# detector_de_IMPACTO.net
KiCad netlist of a schematic drawn in EAGLE
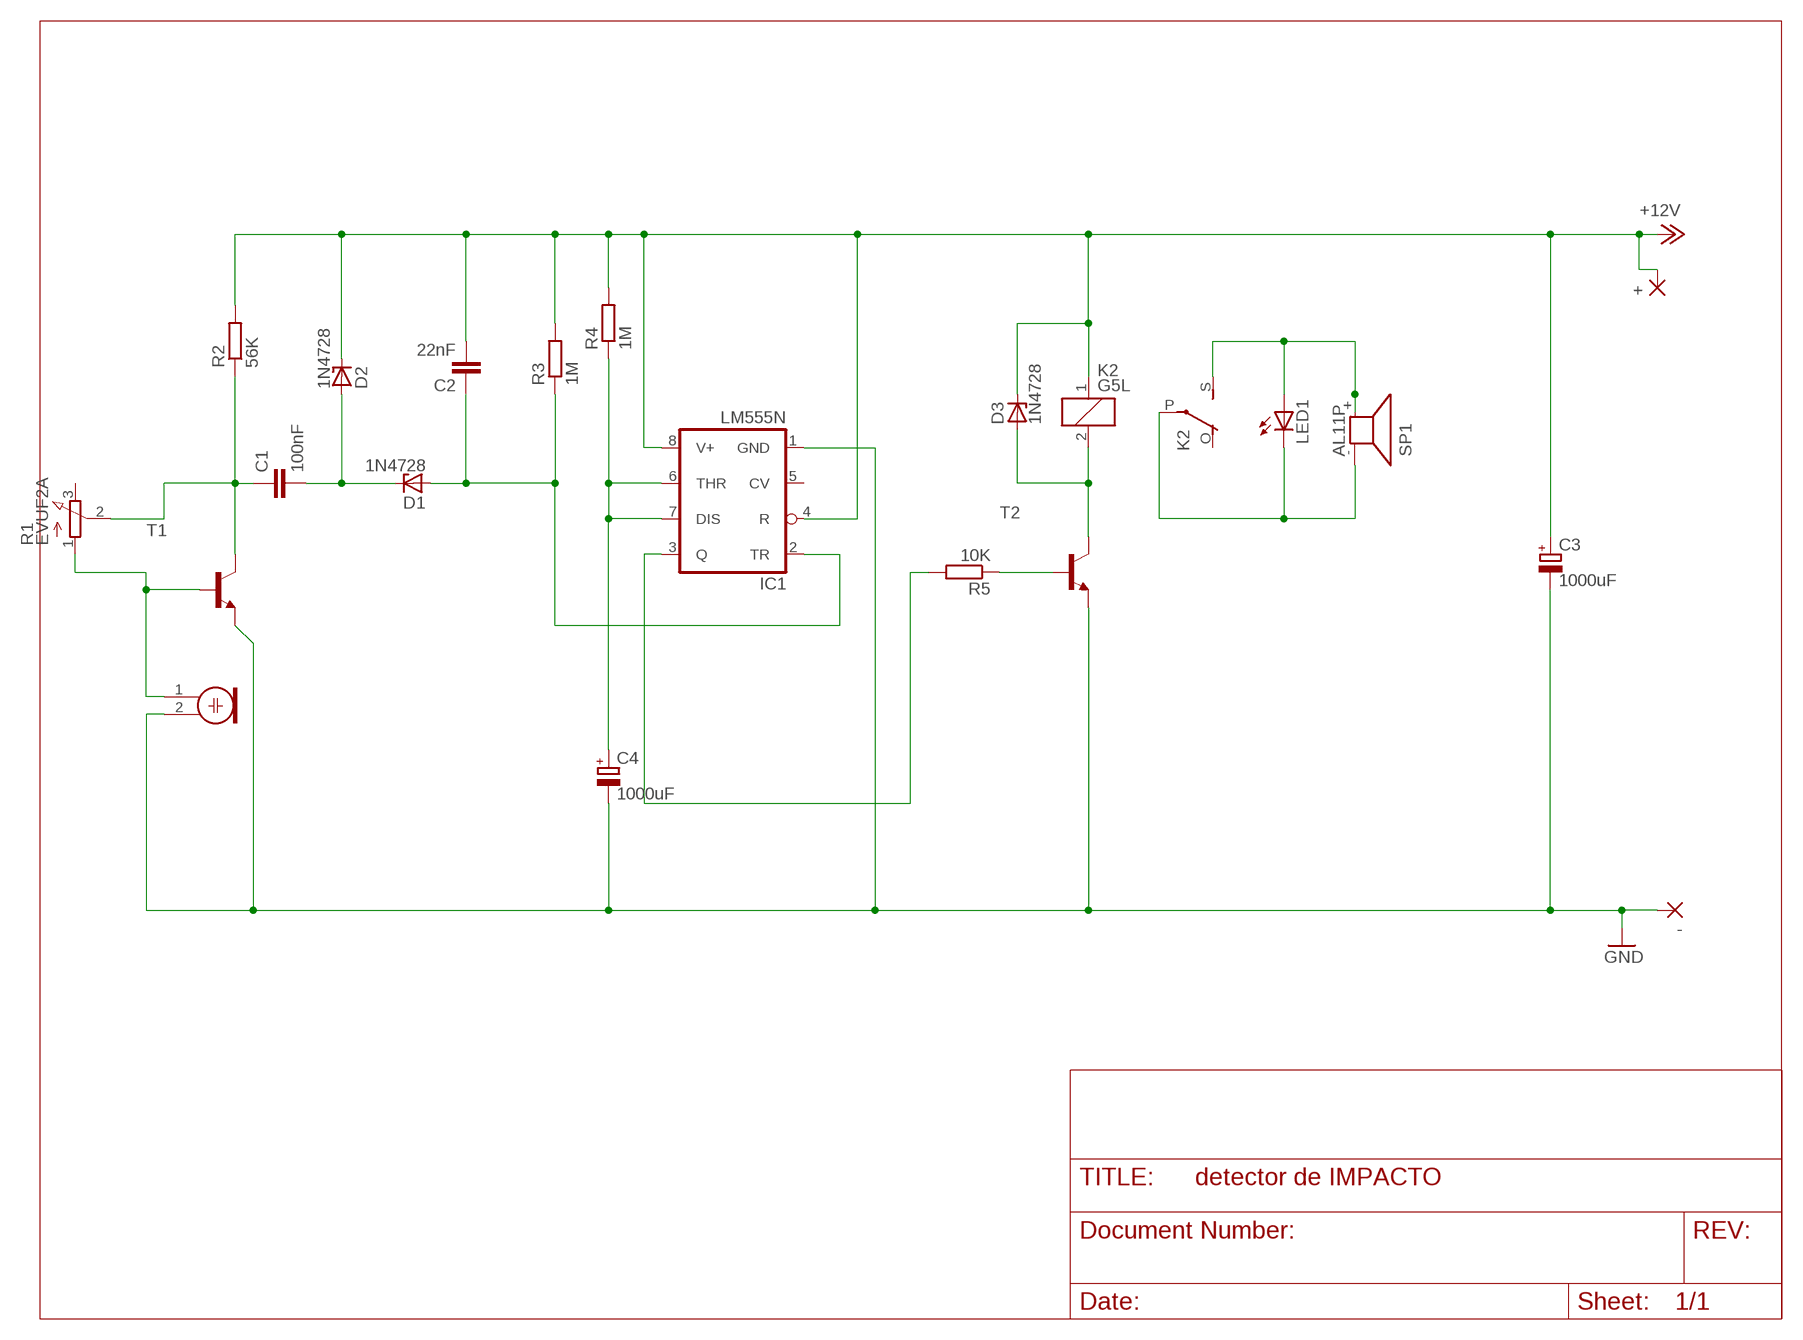
[diagram p0: schematic, sheet 1]

(export (version "E")
  (design (tool "Eeschema 10.0.6"))
  (components
    (comp (ref "+")
      (value "1,6/0,8")
      (footprint "eagle-import:1,6_0,8")
      (libsource (lib "eagle-import") (part "1,6/0,8"))
    )
    (comp (ref "-")
      (value "1,6/0,8")
      (footprint "eagle-import:1,6_0,8")
      (libsource (lib "eagle-import") (part "1,6/0,8"))
    )
    (comp (ref "C1")
      (value "100nF")
      (footprint "eagle-import:C025-024X044")
      (libsource (lib "eagle-import") (part "C-EU025-024X044"))
    )
    (comp (ref "C2")
      (value "22nF")
      (footprint "eagle-import:C025-024X044")
      (libsource (lib "eagle-import") (part "C-EU025-024X044"))
    )
    (comp (ref "C3")
      (value "1000uF")
      (footprint "eagle-import:E5-8,5")
      (libsource (lib "eagle-import") (part "CPOL-EUE5-8.5"))
    )
    (comp (ref "C4")
      (value "1000uF")
      (footprint "eagle-import:E5-8,5")
      (libsource (lib "eagle-import") (part "CPOL-EUE5-8.5"))
    )
    (comp (ref "D1")
      (value "1N4728")
      (footprint "eagle-import:DO41Z10")
      (libsource (lib "eagle-import") (part "1N4728"))
    )
    (comp (ref "D2")
      (value "1N4728")
      (footprint "eagle-import:DO41Z10")
      (libsource (lib "eagle-import") (part "1N4728"))
    )
    (comp (ref "D3")
      (value "1N4728")
      (footprint "eagle-import:DO41Z10")
      (libsource (lib "eagle-import") (part "1N4728"))
    )
    (comp (ref "IC1")
      (value "LM555N")
      (footprint "eagle-import:DIL08")
      (libsource (lib "eagle-import") (part "555NLM"))
    )
    (comp (ref "K2")
      (value "G5L")
      (footprint "eagle-import:G5LE")
      (libsource (lib "eagle-import") (part "G5L"))
    )
    (comp (ref "LED1")
      (value "LED3MM")
      (footprint "eagle-import:LED3MM")
      (libsource (lib "eagle-import") (part "LED3MM"))
    )
    (comp (ref "M1")
      (value "ELECTRET_MICROPHON-WM-64PC/64PK")
      (footprint "eagle-import:WM-64PC_64PK")
      (libsource (lib "eagle-import") (part "ELECTRET_MICROPHON-WM-64PC/64PK"))
    )
    (comp (ref "R1")
      (value "EVUF2A")
      (footprint "eagle-import:EVUF")
      (libsource (lib "eagle-import") (part "EVUAF2"))
    )
    (comp (ref "R2")
      (value "56K")
      (footprint "eagle-import:0207_10")
      (libsource (lib "eagle-import") (part "R-EU_0207/10"))
    )
    (comp (ref "R3")
      (value "1M")
      (footprint "eagle-import:0207_10")
      (libsource (lib "eagle-import") (part "R-EU_0207/10"))
    )
    (comp (ref "R4")
      (value "1M")
      (footprint "eagle-import:0207_10")
      (libsource (lib "eagle-import") (part "R-EU_0207/10"))
    )
    (comp (ref "R5")
      (value "10K")
      (footprint "eagle-import:0207_10")
      (libsource (lib "eagle-import") (part "R-EU_0207/10"))
    )
    (comp (ref "SP1")
      (value "AL11P")
      (footprint "eagle-import:AL11P")
      (libsource (lib "eagle-import") (part "AL11P"))
    )
    (comp (ref "T1")
      (value "BC548-NPN-TO92-CBE")
      (footprint "eagle-import:TO92-CBE")
      (libsource (lib "eagle-import") (part "-NPN-TO92-CBEBC548"))
    )
    (comp (ref "T2")
      (value "BC548-NPN-TO92-CBE")
      (footprint "eagle-import:TO92-CBE")
      (libsource (lib "eagle-import") (part "-NPN-TO92-CBEBC548"))
    )
  )
  (nets
    (net (code "1") (name "+12V") (class "Default")
      (node (ref "+") (pin "1") (pinfunction "P_1") (pintype "passive"))
      (node (ref "C2") (pin "2") (pinfunction "2_2") (pintype "passive"))
      (node (ref "C3") (pin "+") (pinfunction "+_+") (pintype "passive"))
      (node (ref "D2") (pin "C") (pinfunction "C_C") (pintype "passive"))
      (node (ref "D3") (pin "C") (pinfunction "C_C") (pintype "passive"))
      (node (ref "IC1") (pin "4") (pinfunction "R_4") (pintype "input"))
      (node (ref "IC1") (pin "8") (pinfunction "V+_8") (pintype "power_in"))
      (node (ref "K2") (pin "1") (pinfunction "1_1") (pintype "passive"))
      (node (ref "R2") (pin "2") (pinfunction "2_2") (pintype "passive"))
      (node (ref "R3") (pin "2") (pinfunction "2_2") (pintype "passive"))
      (node (ref "R4") (pin "2") (pinfunction "2_2") (pintype "passive"))
    )
    (net (code "2") (name "GND") (class "Default")
      (node (ref "-") (pin "1") (pinfunction "P_1") (pintype "passive"))
      (node (ref "C3") (pin "-") (pinfunction "-_-") (pintype "passive"))
      (node (ref "C4") (pin "-") (pinfunction "-_-") (pintype "passive"))
      (node (ref "IC1") (pin "1") (pinfunction "GND_1") (pintype "power_in"))
      (node (ref "M1") (pin "2") (pinfunction "2_2") (pintype "passive"))
      (node (ref "T1") (pin "E") (pinfunction "E_E") (pintype "passive"))
      (node (ref "T2") (pin "E") (pinfunction "E_E") (pintype "passive"))
    )
    (net (code "3") (name "Net-(C1-Pad2)") (class "Default")
      (node (ref "C1") (pin "2") (pinfunction "2_2") (pintype "passive"))
      (node (ref "D1") (pin "C") (pinfunction "C_C") (pintype "passive"))
      (node (ref "D2") (pin "A") (pinfunction "A_A") (pintype "passive"))
    )
    (net (code "4") (name "Net-(D3-PadA)") (class "Default")
      (node (ref "D3") (pin "A") (pinfunction "A_A") (pintype "passive"))
      (node (ref "K2") (pin "2") (pinfunction "2_2") (pintype "passive"))
      (node (ref "T2") (pin "C") (pinfunction "C_C") (pintype "passive"))
    )
    (net (code "5") (name "Net-(IC1-DIS)") (class "Default")
      (node (ref "C4") (pin "+") (pinfunction "+_+") (pintype "passive"))
      (node (ref "IC1") (pin "6") (pinfunction "THR_6") (pintype "input"))
      (node (ref "IC1") (pin "7") (pinfunction "DIS_7") (pintype "input"))
      (node (ref "R4") (pin "1") (pinfunction "1_1") (pintype "passive"))
    )
    (net (code "6") (name "Net-(IC1-Q)") (class "Default")
      (node (ref "IC1") (pin "3") (pinfunction "Q_3") (pintype "output"))
      (node (ref "R5") (pin "2") (pinfunction "2_2") (pintype "passive"))
    )
    (net (code "7") (name "Net-(IC1-TR)") (class "Default")
      (node (ref "C2") (pin "1") (pinfunction "1_1") (pintype "passive"))
      (node (ref "D1") (pin "A") (pinfunction "A_A") (pintype "passive"))
      (node (ref "IC1") (pin "2") (pinfunction "TR_2") (pintype "input"))
      (node (ref "R3") (pin "1") (pinfunction "1_1") (pintype "passive"))
    )
    (net (code "8") (name "Net-(LED1-C)") (class "Default")
      (node (ref "K2") (pin "P") (pinfunction "P_P") (pintype "passive"))
      (node (ref "LED1") (pin "K") (pinfunction "C_K") (pintype "passive"))
      (node (ref "SP1") (pin "-") (pinfunction "1_-") (pintype "passive"))
    )
    (net (code "9") (name "Net-(R1-A)") (class "Default")
      (node (ref "M1") (pin "1") (pinfunction "1_1") (pintype "passive"))
      (node (ref "R1") (pin "1") (pinfunction "A_1") (pintype "passive"))
      (node (ref "T1") (pin "B") (pinfunction "B_B") (pintype "passive"))
    )
    (net (code "10") (name "Net-(R1-S)") (class "Default")
      (node (ref "C1") (pin "1") (pinfunction "1_1") (pintype "passive"))
      (node (ref "R1") (pin "2") (pinfunction "S_2") (pintype "passive"))
      (node (ref "R2") (pin "1") (pinfunction "1_1") (pintype "passive"))
      (node (ref "T1") (pin "C") (pinfunction "C_C") (pintype "passive"))
    )
    (net (code "11") (name "Net-(R5-Pad1)") (class "Default")
      (node (ref "R5") (pin "1") (pinfunction "1_1") (pintype "passive"))
      (node (ref "T2") (pin "B") (pinfunction "B_B") (pintype "passive"))
    )
    (net (code "12") (name "Net-(SP1-2)") (class "Default")
      (node (ref "K2") (pin "S") (pinfunction "S_S") (pintype "passive"))
      (node (ref "LED1") (pin "A") (pinfunction "A_A") (pintype "passive"))
      (node (ref "SP1") (pin "+") (pinfunction "2_+") (pintype "passive"))
    )
    (net (code "13") (name "unconnected-(IC1-CV-Pad5)") (class "Default")
      (node (ref "IC1") (pin "5") (pinfunction "CV_5") (pintype "input"))
    )
    (net (code "14") (name "unconnected-(K2-PadO)") (class "Default")
      (node (ref "K2") (pin "O") (pinfunction "O_O") (pintype "passive"))
    )
    (net (code "15") (name "unconnected-(R1-E-Pad3)") (class "Default")
      (node (ref "R1") (pin "3") (pinfunction "E_3") (pintype "passive"))
    )
  )
)
